# Filters.net
KiCad netlist of a schematic drawn in Altium Designer
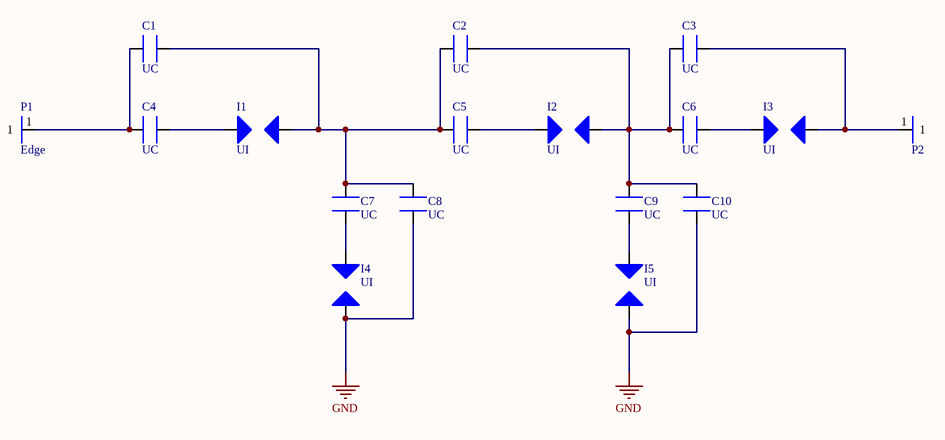
[diagram p0: Filters.SchDoc]

(export (version "E")
  (design (tool "Eeschema 10.0.6"))
  (components
    (comp (ref "C1")
      (value "UC")
      (footprint "Capacitor")
      (libsource (lib "Filters_Schlib") (part "Capacitor"))
    )
    (comp (ref "C2")
      (value "UC")
      (footprint "Capacitor")
      (libsource (lib "Filters_Schlib") (part "Capacitor"))
    )
    (comp (ref "C3")
      (value "UC")
      (footprint "Capacitor")
      (libsource (lib "Filters_Schlib") (part "Capacitor"))
    )
    (comp (ref "C4")
      (value "UC")
      (footprint "Capacitor")
      (libsource (lib "Filters_Schlib") (part "Capacitor"))
    )
    (comp (ref "C5")
      (value "UC")
      (footprint "Capacitor")
      (libsource (lib "Filters_Schlib") (part "Capacitor"))
    )
    (comp (ref "C6")
      (value "UC")
      (footprint "Capacitor")
      (libsource (lib "Filters_Schlib") (part "Capacitor"))
    )
    (comp (ref "C7")
      (value "UC")
      (footprint "Capacitor")
      (libsource (lib "Filters_Schlib") (part "Capacitor"))
    )
    (comp (ref "C8")
      (value "UC")
      (footprint "Capacitor")
      (libsource (lib "Filters_Schlib") (part "Capacitor"))
    )
    (comp (ref "C9")
      (value "UC")
      (footprint "Capacitor")
      (libsource (lib "Filters_Schlib") (part "Capacitor"))
    )
    (comp (ref "C10")
      (value "UC")
      (footprint "Capacitor")
      (libsource (lib "Filters_Schlib") (part "Capacitor"))
    )
    (comp (ref "I1")
      (value "UI")
      (footprint "Inductor Universal")
      (libsource (lib "Filters_Schlib") (part "Inductor"))
    )
    (comp (ref "I2")
      (value "UI")
      (footprint "Inductor Universal")
      (libsource (lib "Filters_Schlib") (part "Inductor"))
    )
    (comp (ref "I3")
      (value "UI")
      (footprint "Inductor Universal")
      (libsource (lib "Filters_Schlib") (part "Inductor"))
    )
    (comp (ref "I4")
      (value "UI")
      (footprint "Inductor Universal")
      (libsource (lib "Filters_Schlib") (part "Inductor"))
    )
    (comp (ref "I5")
      (value "UI")
      (footprint "Inductor Universal")
      (libsource (lib "Filters_Schlib") (part "Inductor"))
    )
    (comp (ref "P1")
      (value "Edge")
      (footprint "Edge Connector")
      (libsource (lib "Filters_Schlib") (part "Edge"))
    )
    (comp (ref "P2")
      (value "Edge")
      (footprint "Edge Connector")
      (libsource (lib "Filters_Schlib") (part "Edge"))
    )
  )
  (nets
    (net (code "1") (name "GND") (class "Default")
      (node (ref "C10") (pin "1") (pinfunction "1_1") (pintype "passive"))
      (node (ref "C8") (pin "1") (pinfunction "1_1") (pintype "passive"))
      (node (ref "I4") (pin "1") (pinfunction "1_1") (pintype "passive"))
      (node (ref "I5") (pin "1") (pinfunction "1_1") (pintype "passive"))
    )
    (net (code "2") (name "Net-(C1-Pad1)") (class "Default")
      (node (ref "C1") (pin "1") (pinfunction "1_1") (pintype "passive"))
      (node (ref "C4") (pin "1") (pinfunction "1_1") (pintype "passive"))
      (node (ref "P1") (pin "1") (pinfunction "1_1") (pintype "passive"))
    )
    (net (code "3") (name "Net-(C1-Pad2)") (class "Default")
      (node (ref "C1") (pin "2") (pinfunction "2_2") (pintype "passive"))
      (node (ref "C2") (pin "1") (pinfunction "1_1") (pintype "passive"))
      (node (ref "C5") (pin "1") (pinfunction "1_1") (pintype "passive"))
      (node (ref "C7") (pin "2") (pinfunction "2_2") (pintype "passive"))
      (node (ref "C8") (pin "2") (pinfunction "2_2") (pintype "passive"))
      (node (ref "I1") (pin "2") (pinfunction "2_2") (pintype "passive"))
    )
    (net (code "4") (name "Net-(C3-Pad2)") (class "Default")
      (node (ref "C3") (pin "2") (pinfunction "2_2") (pintype "passive"))
      (node (ref "I3") (pin "2") (pinfunction "2_2") (pintype "passive"))
      (node (ref "P2") (pin "1") (pinfunction "1_1") (pintype "passive"))
    )
    (net (code "5") (name "Net-(C4-Pad2)") (class "Default")
      (node (ref "C4") (pin "2") (pinfunction "2_2") (pintype "passive"))
      (node (ref "I1") (pin "1") (pinfunction "1_1") (pintype "passive"))
    )
    (net (code "6") (name "Net-(C5-Pad2)") (class "Default")
      (node (ref "C5") (pin "2") (pinfunction "2_2") (pintype "passive"))
      (node (ref "I2") (pin "1") (pinfunction "1_1") (pintype "passive"))
    )
    (net (code "7") (name "Net-(C6-Pad2)") (class "Default")
      (node (ref "C6") (pin "2") (pinfunction "2_2") (pintype "passive"))
      (node (ref "I3") (pin "1") (pinfunction "1_1") (pintype "passive"))
    )
    (net (code "8") (name "Net-(C7-Pad1)") (class "Default")
      (node (ref "C7") (pin "1") (pinfunction "1_1") (pintype "passive"))
      (node (ref "I4") (pin "2") (pinfunction "2_2") (pintype "passive"))
    )
    (net (code "9") (name "Net-(C9-Pad1)") (class "Default")
      (node (ref "C9") (pin "1") (pinfunction "1_1") (pintype "passive"))
      (node (ref "I5") (pin "2") (pinfunction "2_2") (pintype "passive"))
    )
    (net (code "10") (name "Net-(C10-Pad2)") (class "Default")
      (node (ref "C10") (pin "2") (pinfunction "2_2") (pintype "passive"))
      (node (ref "C2") (pin "2") (pinfunction "2_2") (pintype "passive"))
      (node (ref "C3") (pin "1") (pinfunction "1_1") (pintype "passive"))
      (node (ref "C6") (pin "1") (pinfunction "1_1") (pintype "passive"))
      (node (ref "C9") (pin "2") (pinfunction "2_2") (pintype "passive"))
      (node (ref "I2") (pin "2") (pinfunction "2_2") (pintype "passive"))
    )
  )
)
